# Expansion_Headers.net
KiCad netlist of a schematic drawn in Altium Designer
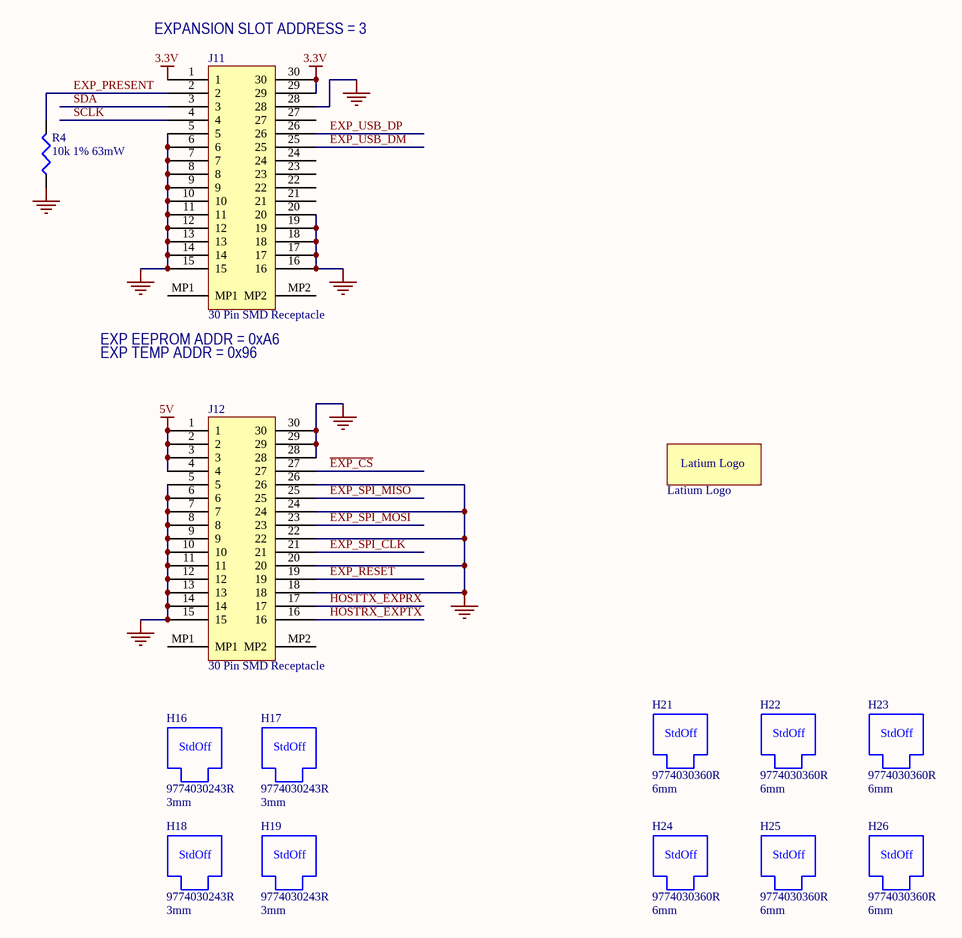
[diagram p0: Expansion Headers.SchDoc]

(export (version "E")
  (design (tool "Eeschema 10.0.6"))
  (components
    (comp (ref "H16")
      (value "9774030243R")
      (footprint "Wurth 9774030243R")
      (description "ROUND STANDOFF M2X0.4 STEEL 3MM")
      (fields (field (name "MANUFACTURER") "Wurth Electronics Inc") (field (name "HEIGHT") "3mm"))
      (libsource (lib "Latium Component Library") (part "SMD M3 Spacer"))
    )
    (comp (ref "H17")
      (value "9774030243R")
      (footprint "Wurth 9774030243R")
      (description "ROUND STANDOFF M2X0.4 STEEL 3MM")
      (fields (field (name "MANUFACTURER") "Wurth Electronics Inc") (field (name "HEIGHT") "3mm"))
      (libsource (lib "Latium Component Library") (part "SMD M3 Spacer"))
    )
    (comp (ref "H18")
      (value "9774030243R")
      (footprint "Wurth 9774030243R")
      (description "ROUND STANDOFF M2X0.4 STEEL 3MM")
      (fields (field (name "MANUFACTURER") "Wurth Electronics Inc") (field (name "HEIGHT") "3mm"))
      (libsource (lib "Latium Component Library") (part "SMD M3 Spacer"))
    )
    (comp (ref "H19")
      (value "9774030243R")
      (footprint "Wurth 9774030243R")
      (description "ROUND STANDOFF M2X0.4 STEEL 3MM")
      (fields (field (name "MANUFACTURER") "Wurth Electronics Inc") (field (name "HEIGHT") "3mm"))
      (libsource (lib "Latium Component Library") (part "SMD M3 Spacer"))
    )
    (comp (ref "H21")
      (value "9774030360R")
      (footprint "Wurth 9774060360R")
      (description "ROUND STANDOFF M3X0.5 STEEL 6MM")
      (fields
        (field (name "MANUFACTURER") "Wurth Electronics Inc")
        (field (name "MANUFACTURER PART NUMBER") "9774060360R")
        (field (name "HEIGHT") "6mm")
      )
      (libsource (lib "Latium Component Library") (part "SMD M3 Spacer"))
    )
    (comp (ref "H22")
      (value "9774030360R")
      (footprint "Wurth 9774060360R")
      (description "ROUND STANDOFF M3X0.5 STEEL 6MM")
      (fields
        (field (name "MANUFACTURER") "Wurth Electronics Inc")
        (field (name "MANUFACTURER PART NUMBER") "9774060360R")
        (field (name "HEIGHT") "6mm")
      )
      (libsource (lib "Latium Component Library") (part "SMD M3 Spacer"))
    )
    (comp (ref "H23")
      (value "9774030360R")
      (footprint "Wurth 9774060360R")
      (description "ROUND STANDOFF M3X0.5 STEEL 6MM")
      (fields
        (field (name "MANUFACTURER") "Wurth Electronics Inc")
        (field (name "MANUFACTURER PART NUMBER") "9774060360R")
        (field (name "HEIGHT") "6mm")
      )
      (libsource (lib "Latium Component Library") (part "SMD M3 Spacer"))
    )
    (comp (ref "H24")
      (value "9774030360R")
      (footprint "Wurth 9774060360R")
      (description "ROUND STANDOFF M3X0.5 STEEL 6MM")
      (fields
        (field (name "MANUFACTURER") "Wurth Electronics Inc")
        (field (name "MANUFACTURER PART NUMBER") "9774060360R")
        (field (name "HEIGHT") "6mm")
      )
      (libsource (lib "Latium Component Library") (part "SMD M3 Spacer"))
    )
    (comp (ref "H25")
      (value "9774030360R")
      (footprint "Wurth 9774060360R")
      (description "ROUND STANDOFF M3X0.5 STEEL 6MM")
      (fields
        (field (name "MANUFACTURER") "Wurth Electronics Inc")
        (field (name "MANUFACTURER PART NUMBER") "9774060360R")
        (field (name "HEIGHT") "6mm")
      )
      (libsource (lib "Latium Component Library") (part "SMD M3 Spacer"))
    )
    (comp (ref "H26")
      (value "9774030360R")
      (footprint "Wurth 9774060360R")
      (description "ROUND STANDOFF M3X0.5 STEEL 6MM")
      (fields
        (field (name "MANUFACTURER") "Wurth Electronics Inc")
        (field (name "MANUFACTURER PART NUMBER") "9774060360R")
        (field (name "HEIGHT") "6mm")
      )
      (libsource (lib "Latium Component Library") (part "SMD M3 Spacer"))
    )
    (comp (ref "H38")
      (value "Latium Logo")
      (footprint "LatiumLogo")
      (libsource (lib "Latium Component Library") (part "Latium Logo"))
    )
    (comp (ref "J11")
      (value "30 Pin SMD Receptacle")
      (footprint "10132798-031100LF")
      (description "CONN RCPT 30POS SMD GOLD")
      (fields
        (field (name "MANUFACTURER") "Amphenol ICC (FCI)")
        (field (name "MANUFACTURER PART NUMBER") "10132798-031100LF")
      )
      (libsource (lib "Latium Component Library") (part "Amphenol 30 Pos BergStak Plug"))
    )
    (comp (ref "J12")
      (value "30 Pin SMD Receptacle")
      (footprint "10132798-031100LF")
      (description "CONN RCPT 30POS SMD GOLD")
      (fields
        (field (name "MANUFACTURER") "Amphenol ICC (FCI)")
        (field (name "MANUFACTURER PART NUMBER") "10132798-031100LF")
      )
      (libsource (lib "Latium Component Library") (part "Amphenol 30 Pos BergStak Plug"))
    )
    (comp (ref "R4")
      (value "10k 1% 63mW")
      (footprint "RESC1005L")
      (description "Resistor")
      (libsource (lib "Miscellaneous Devices") (part "Res3"))
    )
  )
  (nets
    (net (code "1") (name "/EXP_PRESENT") (class "Default")
      (node (ref "J11") (pin "2") (pinfunction "2_2") (pintype "passive"))
      (node (ref "R4") (pin "2") (pinfunction "2_2") (pintype "passive"))
    )
    (net (code "2") (name "/EXP_RESET") (class "Default")
      (node (ref "J12") (pin "19") (pinfunction "19_19") (pintype "passive"))
    )
    (net (code "3") (name "/EXP_SPI_CLK") (class "Default")
      (node (ref "J12") (pin "21") (pinfunction "21_21") (pintype "passive"))
    )
    (net (code "4") (name "/EXP_SPI_MISO") (class "Default")
      (node (ref "J12") (pin "25") (pinfunction "25_25") (pintype "passive"))
    )
    (net (code "5") (name "/EXP_SPI_MOSI") (class "Default")
      (node (ref "J12") (pin "23") (pinfunction "23_23") (pintype "passive"))
    )
    (net (code "6") (name "/EXP_USB_DM") (class "Default")
      (node (ref "J11") (pin "25") (pinfunction "25_25") (pintype "passive"))
    )
    (net (code "7") (name "/EXP_USB_DP") (class "Default")
      (node (ref "J11") (pin "26") (pinfunction "26_26") (pintype "passive"))
    )
    (net (code "8") (name "/HOSTRX_EXPTX") (class "Default")
      (node (ref "J12") (pin "16") (pinfunction "16_16") (pintype "passive"))
    )
    (net (code "9") (name "/HOSTTX_EXPRX") (class "Default")
      (node (ref "J12") (pin "17") (pinfunction "17_17") (pintype "passive"))
    )
    (net (code "10") (name "/SCLK") (class "Default")
      (node (ref "J11") (pin "4") (pinfunction "4_4") (pintype "passive"))
    )
    (net (code "11") (name "/SDA") (class "Default")
      (node (ref "J11") (pin "3") (pinfunction "3_3") (pintype "passive"))
    )
    (net (code "12") (name "/~{EXP_CS}") (class "Default")
      (node (ref "J12") (pin "27") (pinfunction "27_27") (pintype "passive"))
    )
    (net (code "13") (name "3.3V") (class "Default")
      (node (ref "J11") (pin "1") (pinfunction "1_1") (pintype "passive"))
      (node (ref "J11") (pin "29") (pinfunction "29_29") (pintype "passive"))
      (node (ref "J11") (pin "30") (pinfunction "30_30") (pintype "passive"))
    )
    (net (code "14") (name "5V") (class "Default")
      (node (ref "J12") (pin "1") (pinfunction "1_1") (pintype "passive"))
      (node (ref "J12") (pin "2") (pinfunction "2_2") (pintype "passive"))
      (node (ref "J12") (pin "3") (pinfunction "3_3") (pintype "passive"))
      (node (ref "J12") (pin "4") (pinfunction "4_4") (pintype "passive"))
    )
    (net (code "15") (name "GND") (class "Default")
      (node (ref "J11") (pin "10") (pinfunction "10_10") (pintype "passive"))
      (node (ref "J11") (pin "11") (pinfunction "11_11") (pintype "passive"))
      (node (ref "J11") (pin "12") (pinfunction "12_12") (pintype "passive"))
      (node (ref "J11") (pin "13") (pinfunction "13_13") (pintype "passive"))
      (node (ref "J11") (pin "14") (pinfunction "14_14") (pintype "passive"))
      (node (ref "J11") (pin "15") (pinfunction "15_15") (pintype "passive"))
      (node (ref "J11") (pin "16") (pinfunction "16_16") (pintype "passive"))
      (node (ref "J11") (pin "17") (pinfunction "17_17") (pintype "passive"))
      (node (ref "J11") (pin "18") (pinfunction "18_18") (pintype "passive"))
      (node (ref "J11") (pin "19") (pinfunction "19_19") (pintype "passive"))
      (node (ref "J11") (pin "20") (pinfunction "20_20") (pintype "passive"))
      (node (ref "J11") (pin "28") (pinfunction "28_28") (pintype "passive"))
      (node (ref "J11") (pin "5") (pinfunction "5_5") (pintype "passive"))
      (node (ref "J11") (pin "6") (pinfunction "6_6") (pintype "passive"))
      (node (ref "J11") (pin "7") (pinfunction "7_7") (pintype "passive"))
      (node (ref "J11") (pin "8") (pinfunction "8_8") (pintype "passive"))
      (node (ref "J11") (pin "9") (pinfunction "9_9") (pintype "passive"))
      (node (ref "J12") (pin "10") (pinfunction "10_10") (pintype "passive"))
      (node (ref "J12") (pin "11") (pinfunction "11_11") (pintype "passive"))
      (node (ref "J12") (pin "12") (pinfunction "12_12") (pintype "passive"))
      (node (ref "J12") (pin "13") (pinfunction "13_13") (pintype "passive"))
      (node (ref "J12") (pin "14") (pinfunction "14_14") (pintype "passive"))
      (node (ref "J12") (pin "15") (pinfunction "15_15") (pintype "passive"))
      (node (ref "J12") (pin "18") (pinfunction "18_18") (pintype "passive"))
      (node (ref "J12") (pin "20") (pinfunction "20_20") (pintype "passive"))
      (node (ref "J12") (pin "22") (pinfunction "22_22") (pintype "passive"))
      (node (ref "J12") (pin "24") (pinfunction "24_24") (pintype "passive"))
      (node (ref "J12") (pin "26") (pinfunction "26_26") (pintype "passive"))
      (node (ref "J12") (pin "28") (pinfunction "28_28") (pintype "passive"))
      (node (ref "J12") (pin "29") (pinfunction "29_29") (pintype "passive"))
      (node (ref "J12") (pin "30") (pinfunction "30_30") (pintype "passive"))
      (node (ref "J12") (pin "5") (pinfunction "5_5") (pintype "passive"))
      (node (ref "J12") (pin "6") (pinfunction "6_6") (pintype "passive"))
      (node (ref "J12") (pin "7") (pinfunction "7_7") (pintype "passive"))
      (node (ref "J12") (pin "8") (pinfunction "8_8") (pintype "passive"))
      (node (ref "J12") (pin "9") (pinfunction "9_9") (pintype "passive"))
      (node (ref "R4") (pin "1") (pinfunction "1_1") (pintype "passive"))
    )
    (net (code "16") (name "unconnected-(J11-Pad21)") (class "Default")
      (node (ref "J11") (pin "21") (pinfunction "21_21") (pintype "passive"))
    )
    (net (code "17") (name "unconnected-(J11-Pad22)") (class "Default")
      (node (ref "J11") (pin "22") (pinfunction "22_22") (pintype "passive"))
    )
    (net (code "18") (name "unconnected-(J11-Pad23)") (class "Default")
      (node (ref "J11") (pin "23") (pinfunction "23_23") (pintype "passive"))
    )
    (net (code "19") (name "unconnected-(J11-Pad24)") (class "Default")
      (node (ref "J11") (pin "24") (pinfunction "24_24") (pintype "passive"))
    )
    (net (code "20") (name "unconnected-(J11-Pad27)") (class "Default")
      (node (ref "J11") (pin "27") (pinfunction "27_27") (pintype "passive"))
    )
    (net (code "21") (name "unconnected-(J11-PadMP1)") (class "Default")
      (node (ref "J11") (pin "MP1") (pinfunction "MP1_MP1") (pintype "passive"))
    )
    (net (code "22") (name "unconnected-(J11-PadMP2)") (class "Default")
      (node (ref "J11") (pin "MP2") (pinfunction "MP2_MP2") (pintype "passive"))
    )
    (net (code "23") (name "unconnected-(J12-PadMP1)") (class "Default")
      (node (ref "J12") (pin "MP1") (pinfunction "MP1_MP1") (pintype "passive"))
    )
    (net (code "24") (name "unconnected-(J12-PadMP2)") (class "Default")
      (node (ref "J12") (pin "MP2") (pinfunction "MP2_MP2") (pintype "passive"))
    )
  )
)
